# Telemetria_Sensores.net
KiCad netlist of a schematic drawn in Altium Designer
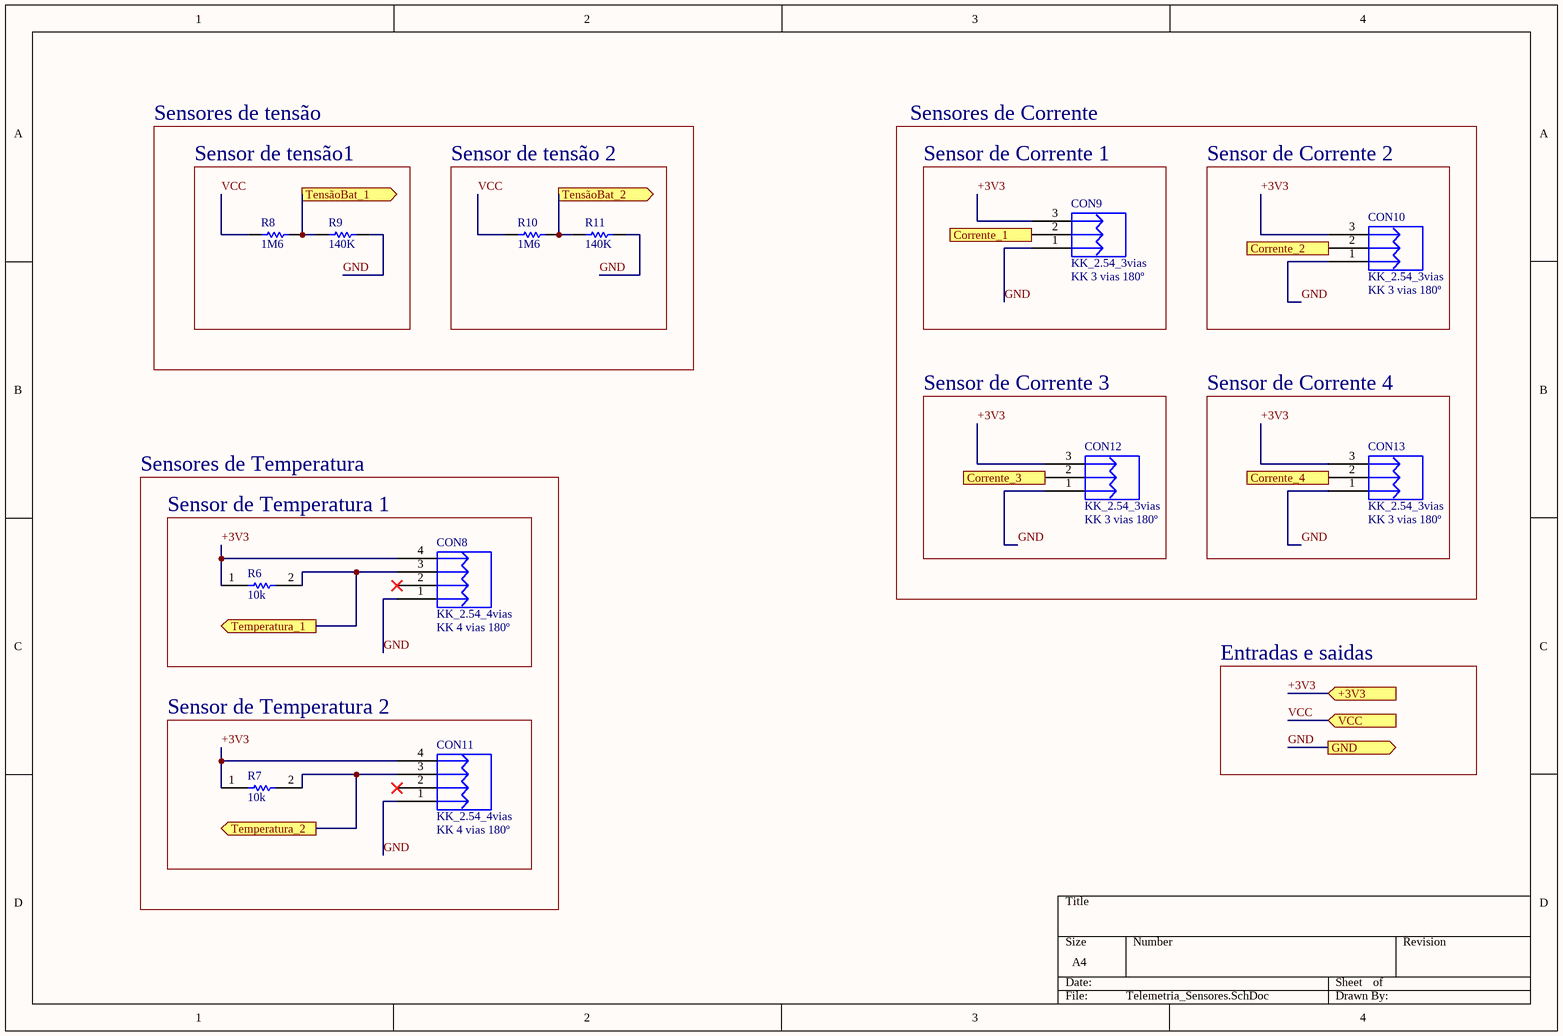
[diagram p0: Telemetria_Sensores.SchDoc]

(export (version "E")
  (design (tool "Eeschema 10.0.6"))
  (components
    (comp (ref "CON8")
      (value "KK_2.54_4vias")
      (footprint "KK_4vias_180°")
      (description "Conector KK 2.54mm 4 vias")
      (fields (field (name "VALOR") "KK 4 vias 180º"))
      (libsource (lib "Conectores_Sch") (part "KK_2.54_4vias"))
    )
    (comp (ref "CON9")
      (value "KK_2.54_3vias")
      (footprint "KK_3vias_180º")
      (description "Conector KK 2.54mm 3 vias")
      (fields (field (name "VALOR") "KK 3 vias 180º"))
      (libsource (lib "Conectores_Sch") (part "KK_2.54_3vias"))
    )
    (comp (ref "CON10")
      (value "KK_2.54_3vias")
      (footprint "KK_3vias_180º")
      (description "Conector KK 2.54mm 3 vias")
      (fields (field (name "VALOR") "KK 3 vias 180º"))
      (libsource (lib "Conectores_Sch") (part "KK_2.54_3vias"))
    )
    (comp (ref "CON11")
      (value "KK_2.54_4vias")
      (footprint "KK_4vias_180°")
      (description "Conector KK 2.54mm 4 vias")
      (fields (field (name "VALOR") "KK 4 vias 180º"))
      (libsource (lib "Conectores_Sch") (part "KK_2.54_4vias"))
    )
    (comp (ref "CON12")
      (value "KK_2.54_3vias")
      (footprint "KK_3vias_180º")
      (description "Conector KK 2.54mm 3 vias")
      (fields (field (name "VALOR") "KK 3 vias 180º"))
      (libsource (lib "Conectores_Sch") (part "KK_2.54_3vias"))
    )
    (comp (ref "CON13")
      (value "KK_2.54_3vias")
      (footprint "KK_3vias_180º")
      (description "Conector KK 2.54mm 3 vias")
      (fields (field (name "VALOR") "KK 3 vias 180º"))
      (libsource (lib "Conectores_Sch") (part "KK_2.54_3vias"))
    )
    (comp (ref "R6")
      (value "10k")
      (footprint "RESC3216X60N")
      (description "Resistor")
      (fields
        (field (name "MANUFACTURER_PART_NUMBER") "CRCW12064K70FKEA")
        (field (name "MOUSER PART NUMBER") "71-CRCW1206-4.7K-E3")
      )
      (libsource (lib "Sinaliza玢o_Official") (part "Resistor 1206"))
    )
    (comp (ref "R7")
      (value "10k")
      (footprint "RESC3216X60N")
      (description "Resistor")
      (fields
        (field (name "MANUFACTURER_PART_NUMBER") "CRCW12064K70FKEA")
        (field (name "MOUSER PART NUMBER") "71-CRCW1206-4.7K-E3")
      )
      (libsource (lib "Sinaliza玢o_Official") (part "Resistor 1206"))
    )
    (comp (ref "R8")
      (value "1M6")
      (footprint "RESISTOR 0603")
      (description "0603")
      (fields
        (field (name "MANUFACTURER") "PANASONIC ELECTRONIC COMPONENTS")
        (field (name "MANUFACTURER PART NUMBER") "ERJ-3GEY0R00V")
      )
      (libsource (lib "RoboHospitalar") (part "RES 0603 5%"))
    )
    (comp (ref "R9")
      (value "140K")
      (footprint "RESISTOR 0805")
      (description "0805")
      (fields
        (field (name "MANUFACTURER") "PANASONIC ELECTRONIC COMPONENTS")
        (field (name "MANUFACTURER PART NUMBER") "ERJ-3GEY0R00V")
      )
      (libsource (lib "RoboHospitalar") (part "RES 0805 5%"))
    )
    (comp (ref "R10")
      (value "1M6")
      (footprint "RESISTOR 0603")
      (description "0603")
      (fields
        (field (name "MANUFACTURER") "PANASONIC ELECTRONIC COMPONENTS")
        (field (name "MANUFACTURER PART NUMBER") "ERJ-3GEY0R00V")
      )
      (libsource (lib "RoboHospitalar") (part "RES 0603 5%"))
    )
    (comp (ref "R11")
      (value "140K")
      (footprint "RESISTOR 0805")
      (description "0805")
      (fields
        (field (name "MANUFACTURER") "PANASONIC ELECTRONIC COMPONENTS")
        (field (name "MANUFACTURER PART NUMBER") "ERJ-3GEY0R00V")
      )
      (libsource (lib "RoboHospitalar") (part "RES 0805 5%"))
    )
  )
  (nets
    (net (code "1") (name "/+3V3") (class "Default")
      (node (ref "CON10") (pin "3") (pintype "passive"))
      (node (ref "CON11") (pin "4") (pintype "passive"))
      (node (ref "CON12") (pin "3") (pintype "passive"))
      (node (ref "CON13") (pin "3") (pintype "passive"))
      (node (ref "CON8") (pin "4") (pintype "passive"))
      (node (ref "CON9") (pin "3") (pintype "passive"))
      (node (ref "R6") (pin "1") (pinfunction "1_1") (pintype "passive"))
      (node (ref "R7") (pin "1") (pinfunction "1_1") (pintype "passive"))
    )
    (net (code "2") (name "/Corrente_1") (class "Default") (node (ref "CON9") (pin "2") (pintype "passive")))
    (net (code "3") (name "/Corrente_2") (class "Default") (node (ref "CON10") (pin "2") (pintype "passive")))
    (net (code "4") (name "/Corrente_3") (class "Default") (node (ref "CON12") (pin "2") (pintype "passive")))
    (net (code "5") (name "/Corrente_4") (class "Default") (node (ref "CON13") (pin "2") (pintype "passive")))
    (net (code "6") (name "/GND") (class "Default")
      (node (ref "CON10") (pin "1") (pintype "passive"))
      (node (ref "CON11") (pin "1") (pintype "passive"))
      (node (ref "CON12") (pin "1") (pintype "passive"))
      (node (ref "CON13") (pin "1") (pintype "passive"))
      (node (ref "CON8") (pin "1") (pintype "passive"))
      (node (ref "CON9") (pin "1") (pintype "passive"))
      (node (ref "R11") (pin "2") (pinfunction "2_2") (pintype "passive"))
      (node (ref "R9") (pin "2") (pinfunction "2_2") (pintype "passive"))
    )
    (net (code "7") (name "/Temperatura_1") (class "Default")
      (node (ref "CON8") (pin "3") (pintype "passive"))
      (node (ref "R6") (pin "2") (pinfunction "2_2") (pintype "passive"))
    )
    (net (code "8") (name "/Temperatura_2") (class "Default")
      (node (ref "CON11") (pin "3") (pintype "passive"))
      (node (ref "R7") (pin "2") (pinfunction "2_2") (pintype "passive"))
    )
    (net (code "9") (name "/TensãoBat_1") (class "Default")
      (node (ref "R8") (pin "2") (pinfunction "2_2") (pintype "passive"))
      (node (ref "R9") (pin "1") (pinfunction "1_1") (pintype "passive"))
    )
    (net (code "10") (name "/TensãoBat_2") (class "Default")
      (node (ref "R10") (pin "2") (pinfunction "2_2") (pintype "passive"))
      (node (ref "R11") (pin "1") (pinfunction "1_1") (pintype "passive"))
    )
    (net (code "11") (name "/VCC") (class "Default")
      (node (ref "R10") (pin "1") (pinfunction "1_1") (pintype "passive"))
      (node (ref "R8") (pin "1") (pinfunction "1_1") (pintype "passive"))
    )
    (net (code "12") (name "unconnected-(CON8-Pad2)") (class "Default")
      (node (ref "CON8") (pin "2") (pintype "passive+no_connect"))
    )
    (net (code "13") (name "unconnected-(CON11-Pad2)") (class "Default")
      (node (ref "CON11") (pin "2") (pintype "passive+no_connect"))
    )
  )
)
